# HT1017-MAIN.net
KiCad netlist of a schematic drawn in Altium Designer
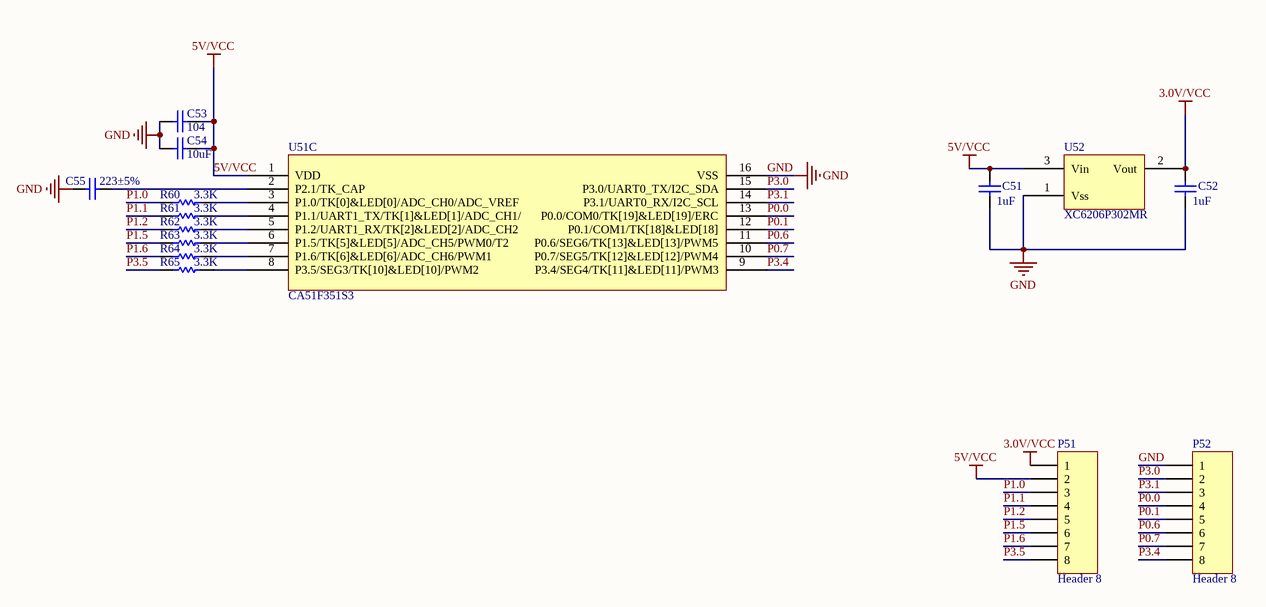
[diagram p0: HT1017-MAIN.SchDoc]

(export (version "E")
  (design (tool "Eeschema 10.0.6"))
  (components
    (comp (ref "C51")
      (value "1uF")
      (footprint "C 0603_L")
      (description "电容")
      (fields (field (name "Comment") "Cap") (field (name "PUBLISHER") "Altium Limited"))
      (libsource (lib "Miscellaneous Devices") (part "Cap"))
    )
    (comp (ref "C52")
      (value "1uF")
      (footprint "C 0603_L")
      (description "电容")
      (fields (field (name "Comment") "Cap") (field (name "PUBLISHER") "Altium Limited"))
      (libsource (lib "Miscellaneous Devices") (part "Cap"))
    )
    (comp (ref "C53")
      (value "104")
      (footprint "C 0603_L")
      (description "电容")
      (fields (field (name "Comment") "Cap") (field (name "PUBLISHER") "Altium Limited"))
      (libsource (lib "Miscellaneous Devices") (part "Cap"))
    )
    (comp (ref "C54")
      (value "10uF")
      (footprint "C 0805_L")
      (description "电容")
      (fields (field (name "Comment") "Cap") (field (name "PUBLISHER") "Altium Limited"))
      (libsource (lib "Miscellaneous Devices") (part "Cap"))
    )
    (comp (ref "C55")
      (value "223±5%")
      (footprint "C 0603_L")
      (description "电容")
      (fields (field (name "Comment") "Cap") (field (name "PUBLISHER") "Altium Limited"))
      (libsource (lib "Miscellaneous Devices") (part "Cap"))
    )
    (comp (ref "P51")
      (value "Header 8")
      (footprint "HDR1X8")
      (description "Header, 8-Pin")
      (fields (field (name "PUBLISHER") "Altium Limited"))
      (libsource (lib "Miscellaneous Connectors") (part "Header 8"))
    )
    (comp (ref "P52")
      (value "Header 8")
      (footprint "HDR1X8")
      (description "Header, 8-Pin")
      (fields (field (name "PUBLISHER") "Altium Limited"))
      (libsource (lib "Miscellaneous Connectors") (part "Header 8"))
    )
    (comp (ref "R60")
      (value "3.3K")
      (footprint "R 0603_L")
      (description "电阻")
      (fields (field (name "Comment") "Res1") (field (name "PUBLISHER") "Altium Limited"))
      (libsource (lib "Miscellaneous Devices") (part "Res1"))
    )
    (comp (ref "R61")
      (value "3.3K")
      (footprint "R 0603_L")
      (description "电阻")
      (fields (field (name "Comment") "Res1") (field (name "PUBLISHER") "Altium Limited"))
      (libsource (lib "Miscellaneous Devices") (part "Res1"))
    )
    (comp (ref "R62")
      (value "3.3K")
      (footprint "R 0603_L")
      (description "电阻")
      (fields (field (name "Comment") "Res1") (field (name "PUBLISHER") "Altium Limited"))
      (libsource (lib "Miscellaneous Devices") (part "Res1"))
    )
    (comp (ref "R63")
      (value "3.3K")
      (footprint "R 0603_L")
      (description "电阻")
      (fields (field (name "Comment") "Res1") (field (name "PUBLISHER") "Altium Limited"))
      (libsource (lib "Miscellaneous Devices") (part "Res1"))
    )
    (comp (ref "R64")
      (value "3.3K")
      (footprint "R 0603_L")
      (description "电阻")
      (fields (field (name "Comment") "Res1") (field (name "PUBLISHER") "Altium Limited"))
      (libsource (lib "Miscellaneous Devices") (part "Res1"))
    )
    (comp (ref "R65")
      (value "3.3K")
      (footprint "R 0603_L")
      (description "电阻")
      (fields (field (name "Comment") "Res1") (field (name "PUBLISHER") "Altium Limited"))
      (libsource (lib "Miscellaneous Devices") (part "Res1"))
    )
    (comp (ref "U51")
      (value "CA51F351S3")
      (footprint "SOP16_L")
      (libsource (lib "HT_SHUIHU") (part "CA51F351S3"))
    )
    (comp (ref "U52")
      (value "XC6206P302MR")
      (footprint "SOT23-3L")
      (description "稳压IC")
      (libsource (lib "shajunbei") (part "XC6206P302MR"))
    )
  )
  (nets
    (net (code "1") (name "/P0.0") (class "Default")
      (node (ref "P52") (pin "4") (pinfunction "4_4") (pintype "passive"))
      (node (ref "U51") (pin "13") (pinfunction "P0.0/COM0/TK[19]&LED[19]/ERC_13") (pintype "passive"))
    )
    (net (code "2") (name "/P0.1") (class "Default")
      (node (ref "P52") (pin "5") (pinfunction "5_5") (pintype "passive"))
      (node (ref "U51") (pin "12") (pinfunction "P0.1/COM1/TK[18]&LED[18]_12") (pintype "passive"))
    )
    (net (code "3") (name "/P0.6") (class "Default")
      (node (ref "P52") (pin "6") (pinfunction "6_6") (pintype "passive"))
      (node (ref "U51") (pin "11") (pinfunction "P0.6/SEG6/TK[13]&LED[13]/PWM5_11") (pintype "passive"))
    )
    (net (code "4") (name "/P0.7") (class "Default")
      (node (ref "P52") (pin "7") (pinfunction "7_7") (pintype "passive"))
      (node (ref "U51") (pin "10") (pinfunction "P0.7/SEG5/TK[12]&LED[12]/PWM4_10") (pintype "passive"))
    )
    (net (code "5") (name "/P1.0") (class "Default")
      (node (ref "P51") (pin "3") (pinfunction "3_3") (pintype "passive"))
      (node (ref "R60") (pin "1") (pinfunction "1_1") (pintype "passive"))
    )
    (net (code "6") (name "/P1.1") (class "Default")
      (node (ref "P51") (pin "4") (pinfunction "4_4") (pintype "passive"))
      (node (ref "R61") (pin "1") (pinfunction "1_1") (pintype "passive"))
    )
    (net (code "7") (name "/P1.2") (class "Default")
      (node (ref "P51") (pin "5") (pinfunction "5_5") (pintype "passive"))
      (node (ref "R62") (pin "1") (pinfunction "1_1") (pintype "passive"))
    )
    (net (code "8") (name "/P1.5") (class "Default")
      (node (ref "P51") (pin "6") (pinfunction "6_6") (pintype "passive"))
      (node (ref "R63") (pin "1") (pinfunction "1_1") (pintype "passive"))
    )
    (net (code "9") (name "/P1.6") (class "Default")
      (node (ref "P51") (pin "7") (pinfunction "7_7") (pintype "passive"))
      (node (ref "R64") (pin "1") (pinfunction "1_1") (pintype "passive"))
    )
    (net (code "10") (name "/P3.0") (class "Default")
      (node (ref "P52") (pin "2") (pinfunction "2_2") (pintype "passive"))
      (node (ref "U51") (pin "15") (pinfunction "P3.0/UART0_TX/I2C_SDA_15") (pintype "passive"))
    )
    (net (code "11") (name "/P3.1") (class "Default")
      (node (ref "P52") (pin "3") (pinfunction "3_3") (pintype "passive"))
      (node (ref "U51") (pin "14") (pinfunction "P3.1/UART0_RX/I2C_SCL_14") (pintype "passive"))
    )
    (net (code "12") (name "/P3.4") (class "Default")
      (node (ref "P52") (pin "8") (pinfunction "8_8") (pintype "passive"))
      (node (ref "U51") (pin "9") (pinfunction "P3.4/SEG4/TK[11]&LED[11]/PWM3_9") (pintype "passive"))
    )
    (net (code "13") (name "/P3.5") (class "Default")
      (node (ref "P51") (pin "8") (pinfunction "8_8") (pintype "passive"))
      (node (ref "R65") (pin "1") (pinfunction "1_1") (pintype "passive"))
    )
    (net (code "14") (name "3.0V{slash}VCC") (class "Default")
      (node (ref "C52") (pin "2") (pinfunction "2_2") (pintype "passive"))
      (node (ref "P51") (pin "1") (pinfunction "1_1") (pintype "passive"))
      (node (ref "U52") (pin "2") (pinfunction "Vout_2") (pintype "passive"))
    )
    (net (code "15") (name "5V{slash}VCC") (class "Default")
      (node (ref "C51") (pin "2") (pinfunction "2_2") (pintype "passive"))
      (node (ref "C53") (pin "2") (pinfunction "2_2") (pintype "passive"))
      (node (ref "C54") (pin "2") (pinfunction "2_2") (pintype "passive"))
      (node (ref "P51") (pin "2") (pinfunction "2_2") (pintype "passive"))
      (node (ref "U51") (pin "1") (pinfunction "VDD_1") (pintype "passive"))
      (node (ref "U52") (pin "3") (pinfunction "Vin_3") (pintype "passive"))
    )
    (net (code "16") (name "GND") (class "Default")
      (node (ref "C51") (pin "1") (pinfunction "1_1") (pintype "passive"))
      (node (ref "C52") (pin "1") (pinfunction "1_1") (pintype "passive"))
      (node (ref "C53") (pin "1") (pinfunction "1_1") (pintype "passive"))
      (node (ref "C54") (pin "1") (pinfunction "1_1") (pintype "passive"))
      (node (ref "C55") (pin "1") (pinfunction "1_1") (pintype "passive"))
      (node (ref "P52") (pin "1") (pinfunction "1_1") (pintype "passive"))
      (node (ref "U51") (pin "16") (pinfunction "VSS_16") (pintype "passive"))
      (node (ref "U52") (pin "1") (pinfunction "Vss_1") (pintype "passive"))
    )
    (net (code "17") (name "Net-(U51C-P1.0{slash}TK[0]&LED[0]{slash}ADC_CH0{slash}ADC_VREF)") (class "Default")
      (node (ref "R60") (pin "2") (pinfunction "2_2") (pintype "passive"))
      (node (ref "U51") (pin "3") (pinfunction "P1.0/TK[0]&LED[0]/ADC_CH0/ADC_VREF_3") (pintype "passive"))
    )
    (net (code "18") (name "Net-(U51C-P1.1{slash}UART1_TX{slash}TK[1]&LED[1]{slash}ADC_CH1{slash})") (class "Default")
      (node (ref "R61") (pin "2") (pinfunction "2_2") (pintype "passive"))
      (node (ref "U51") (pin "4") (pinfunction "P1.1/UART1_TX/TK[1]&LED[1]/ADC_CH1/_4") (pintype "passive"))
    )
    (net (code "19") (name "Net-(U51C-P1.2{slash}UART1_RX{slash}TK[2]&LED[2]{slash}ADC_CH2)") (class "Default")
      (node (ref "R62") (pin "2") (pinfunction "2_2") (pintype "passive"))
      (node (ref "U51") (pin "5") (pinfunction "P1.2/UART1_RX/TK[2]&LED[2]/ADC_CH2_5") (pintype "passive"))
    )
    (net (code "20") (name "Net-(U51C-P1.5{slash}TK[5]&LED[5]{slash}ADC_CH5{slash}PWM0{slash}T2)") (class "Default")
      (node (ref "R63") (pin "2") (pinfunction "2_2") (pintype "passive"))
      (node (ref "U51") (pin "6") (pinfunction "P1.5/TK[5]&LED[5]/ADC_CH5/PWM0/T2_6") (pintype "passive"))
    )
    (net (code "21") (name "Net-(U51C-P1.6{slash}TK[6]&LED[6]{slash}ADC_CH6{slash}PWM1)") (class "Default")
      (node (ref "R64") (pin "2") (pinfunction "2_2") (pintype "passive"))
      (node (ref "U51") (pin "7") (pinfunction "P1.6/TK[6]&LED[6]/ADC_CH6/PWM1_7") (pintype "passive"))
    )
    (net (code "22") (name "Net-(U51C-P2.1{slash}TK_CAP)") (class "Default")
      (node (ref "C55") (pin "2") (pinfunction "2_2") (pintype "passive"))
      (node (ref "U51") (pin "2") (pinfunction "P2.1/TK_CAP_2") (pintype "passive"))
    )
    (net (code "23") (name "Net-(U51C-P3.5{slash}SEG3{slash}TK[10]&LED[10]{slash}PWM2)") (class "Default")
      (node (ref "R65") (pin "2") (pinfunction "2_2") (pintype "passive"))
      (node (ref "U51") (pin "8") (pinfunction "P3.5/SEG3/TK[10]&LED[10]/PWM2_8") (pintype "passive"))
    )
  )
)
